# TeamD_PDSfinal_m.net
KiCad netlist of a schematic drawn in EAGLE
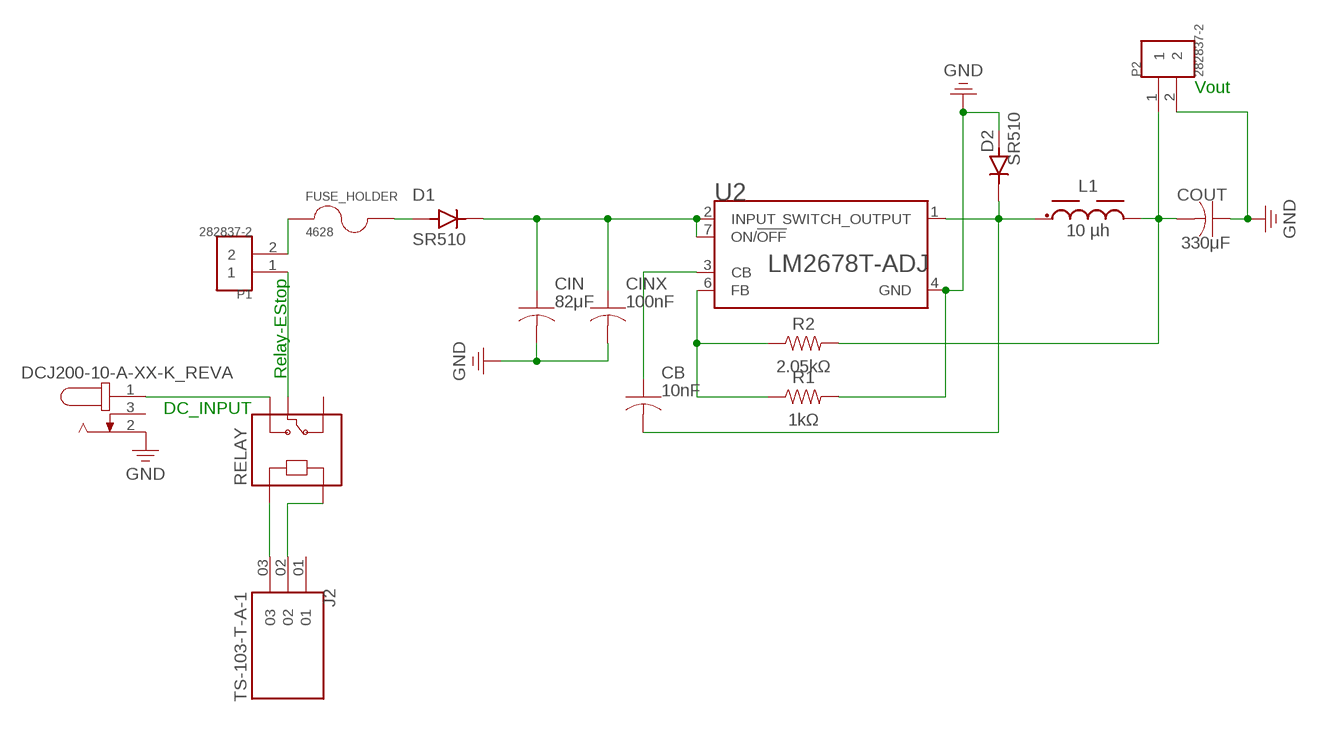
[diagram p0: schematic, sheet 1]

(export (version "E")
  (design (tool "Eeschema 10.0.6"))
  (components
    (comp (ref "CB")
      (value "10nF")
      (footprint "eagle-import:CAPRD550W60D1025H1250B")
      (libsource (lib "eagle-import") (part "C-USRADIAL-12.5MM-DIA_"))
    )
    (comp (ref "CIN")
      (value "82μF")
      (footprint "eagle-import:CAPRD550W60D1025H1250B")
      (libsource (lib "eagle-import") (part "C-USRADIAL-12.5MM-DIA_"))
    )
    (comp (ref "CINX")
      (value "100nF")
      (footprint "eagle-import:CAPRD550W60D1025H1250B")
      (libsource (lib "eagle-import") (part "C-USRADIAL-12.5MM-DIA_"))
    )
    (comp (ref "COUT")
      (value "330μF")
      (footprint "eagle-import:CAPRD550W60D1025H1250B")
      (libsource (lib "eagle-import") (part "C-USRADIAL-12.5MM-DIA_"))
    )
    (comp (ref "D1")
      (value "SR510")
      (footprint "eagle-import:DIOAD1990W125L900D530")
      (fields (field (name "MF") "Multicomp") (field (name "MP") "SR5100"))
      (libsource (lib "eagle-import") (part "SR510"))
    )
    (comp (ref "D2")
      (value "SR510")
      (footprint "eagle-import:DIOAD1990W125L900D530")
      (fields (field (name "MF") "Multicomp") (field (name "MP") "SR5100"))
      (libsource (lib "eagle-import") (part "SR510"))
    )
    (comp (ref "FUSE_HOLDER")
      (value "4628")
      (footprint "eagle-import:FUSE_4628")
      (fields (field (name "MANUFACTURER") "Keystone"))
      (libsource (lib "eagle-import") (part "4628"))
    )
    (comp (ref "J1")
      (value "DCJ200-10-A-XX-K_REVA")
      (footprint "eagle-import:GCT_DCJ200-10-A-XX-K_REVA")
      (fields (field (name "MF") "Global Connector Technology") (field (name "MP") "DCJ200-10-A-K1-K"))
      (libsource (lib "eagle-import") (part "DCJ200-10-A-XX-K_REVA"))
    )
    (comp (ref "J2")
      (value "TS-103-T-A-1")
      (footprint "eagle-import:SAMTEC_TS-103-T-A-1")
      (fields (field (name "MF") "Samtec"))
      (libsource (lib "eagle-import") (part "TS-103-T-A-1"))
    )
    (comp (ref "L1")
      (value "10 µh")
      (footprint "eagle-import:WE-TIS_1111")
      (fields (field (name "MF") "Würth Elektronik") (field (name "MP") "7447471100"))
      (libsource (lib "eagle-import") (part "WE-TIS_1111"))
    )
    (comp (ref "P1")
      (value "282837-2")
      (footprint "eagle-import:TE_282837-2")
      (fields (field (name "MF") "TE Connectivity"))
      (libsource (lib "eagle-import") (part "282837-2"))
    )
    (comp (ref "P2")
      (value "282837-2")
      (footprint "eagle-import:TE_282837-2")
      (fields (field (name "MF") "TE Connectivity"))
      (libsource (lib "eagle-import") (part "282837-2"))
    )
    (comp (ref "R1")
      (value "1kΩ")
      (footprint "eagle-import:RESAD724W46L381D178B")
      (libsource (lib "eagle-import") (part "R-USAXIAL-7.2MM-PITCH_"))
    )
    (comp (ref "R2")
      (value "2.05kΩ")
      (footprint "eagle-import:RESAD724W46L381D178B")
      (libsource (lib "eagle-import") (part "R-USAXIAL-7.2MM-PITCH_"))
    )
    (comp (ref "RELAY")
      (value "SRD-05VDC-SL-C")
      (footprint "eagle-import:RELAY_SRD-05VDC-SL-C")
      (fields (field (name "MF") "Songle Relay"))
      (libsource (lib "eagle-import") (part "SRD-05VDC-SL-C"))
    )
    (comp (ref "U2")
      (value "LM2678T-ADJ")
      (footprint "eagle-import:TO127P1041X469X2199-7N")
      (fields (field (name "MF") "Texas Instruments"))
      (libsource (lib "eagle-import") (part "LM2678T-ADJ"))
    )
  )
  (nets
    (net (code "1") (name "GND") (class "Default")
      (node (ref "CIN") (pin "2") (pinfunction "2_2") (pintype "passive"))
      (node (ref "CINX") (pin "2") (pinfunction "2_2") (pintype "passive"))
      (node (ref "COUT") (pin "1") (pinfunction "1_1") (pintype "passive"))
      (node (ref "D2") (pin "A") (pinfunction "A_A") (pintype "passive"))
      (node (ref "J1") (pin "2") (pinfunction "2_2") (pintype "passive"))
      (node (ref "P2") (pin "2") (pinfunction "2_2") (pintype "passive"))
      (node (ref "R1") (pin "2") (pinfunction "2_2") (pintype "passive"))
      (node (ref "U2") (pin "4") (pinfunction "GND_4") (pintype "power_in"))
    )
    (net (code "2") (name "Net-(COUT-Pad2)") (class "Default")
      (node (ref "COUT") (pin "2") (pinfunction "2_2") (pintype "passive"))
      (node (ref "L1") (pin "2") (pinfunction "2_2") (pintype "passive"))
      (node (ref "P2") (pin "1") (pinfunction "1_1") (pintype "passive"))
      (node (ref "R2") (pin "2") (pinfunction "2_2") (pintype "passive"))
    )
    (net (code "3") (name "Net-(D1-K)") (class "Default")
      (node (ref "CIN") (pin "1") (pinfunction "1_1") (pintype "passive"))
      (node (ref "CINX") (pin "1") (pinfunction "1_1") (pintype "passive"))
      (node (ref "D1") (pin "C") (pinfunction "K_C") (pintype "passive"))
      (node (ref "U2") (pin "2") (pinfunction "INPUT_2") (pintype "input"))
      (node (ref "U2") (pin "7") (pinfunction "ON/~{OFF}_7") (pintype "input"))
    )
    (net (code "4") (name "Net-(D1-PadA)") (class "Default")
      (node (ref "D1") (pin "A") (pinfunction "A_A") (pintype "passive"))
      (node (ref "FUSE_HOLDER") (pin "2") (pinfunction "2_2") (pintype "passive"))
    )
    (net (code "5") (name "Net-(D2-K)") (class "Default")
      (node (ref "CB") (pin "2") (pinfunction "2_2") (pintype "passive"))
      (node (ref "D2") (pin "C") (pinfunction "K_C") (pintype "passive"))
      (node (ref "L1") (pin "1") (pinfunction "1_1") (pintype "passive"))
      (node (ref "U2") (pin "1") (pinfunction "SWITCH_OUTPUT_1") (pintype "output"))
    )
    (net (code "6") (name "Net-(FUSE_HOLDER-Pad1)") (class "Default")
      (node (ref "FUSE_HOLDER") (pin "1") (pinfunction "1_1") (pintype "passive"))
      (node (ref "P1") (pin "2") (pinfunction "2_2") (pintype "passive"))
    )
    (net (code "7") (name "Net-(J1-Pad1)") (class "Default")
      (node (ref "J1") (pin "1") (pinfunction "1_1") (pintype "passive"))
      (node (ref "RELAY") (pin "NO") (pinfunction "NO_NO") (pintype "passive"))
    )
    (net (code "8") (name "Net-(J2-Pad02)") (class "Default")
      (node (ref "J2") (pin "02") (pinfunction "02_02") (pintype "passive"))
      (node (ref "RELAY") (pin "A2") (pinfunction "A2_A2") (pintype "passive"))
    )
    (net (code "9") (name "Net-(J2-Pad03)") (class "Default")
      (node (ref "J2") (pin "03") (pinfunction "03_03") (pintype "passive"))
      (node (ref "RELAY") (pin "A1") (pinfunction "A1_A1") (pintype "passive"))
    )
    (net (code "10") (name "Net-(P1-Pad1)") (class "Default")
      (node (ref "P1") (pin "1") (pinfunction "1_1") (pintype "passive"))
      (node (ref "RELAY") (pin "COM") (pinfunction "COM_COM") (pintype "passive"))
    )
    (net (code "11") (name "Net-(U2-CB)") (class "Default")
      (node (ref "CB") (pin "1") (pinfunction "1_1") (pintype "passive"))
      (node (ref "U2") (pin "3") (pinfunction "CB_3") (pintype "input"))
    )
    (net (code "12") (name "Net-(U2-FB)") (class "Default")
      (node (ref "R1") (pin "1") (pinfunction "1_1") (pintype "passive"))
      (node (ref "R2") (pin "1") (pinfunction "1_1") (pintype "passive"))
      (node (ref "U2") (pin "6") (pinfunction "FB_6") (pintype "input"))
    )
    (net (code "13") (name "unconnected-(J1-Pad3)") (class "Default")
      (node (ref "J1") (pin "3") (pinfunction "3_3") (pintype "passive"))
    )
    (net (code "14") (name "unconnected-(J2-Pad01)") (class "Default")
      (node (ref "J2") (pin "01") (pinfunction "01_01") (pintype "passive"))
    )
    (net (code "15") (name "unconnected-(RELAY-PadNC)") (class "Default")
      (node (ref "RELAY") (pin "NC") (pinfunction "NC_NC") (pintype "passive"))
    )
  )
)
